# Amp_Measurement.net
KiCad netlist of a schematic drawn in Altium Designer
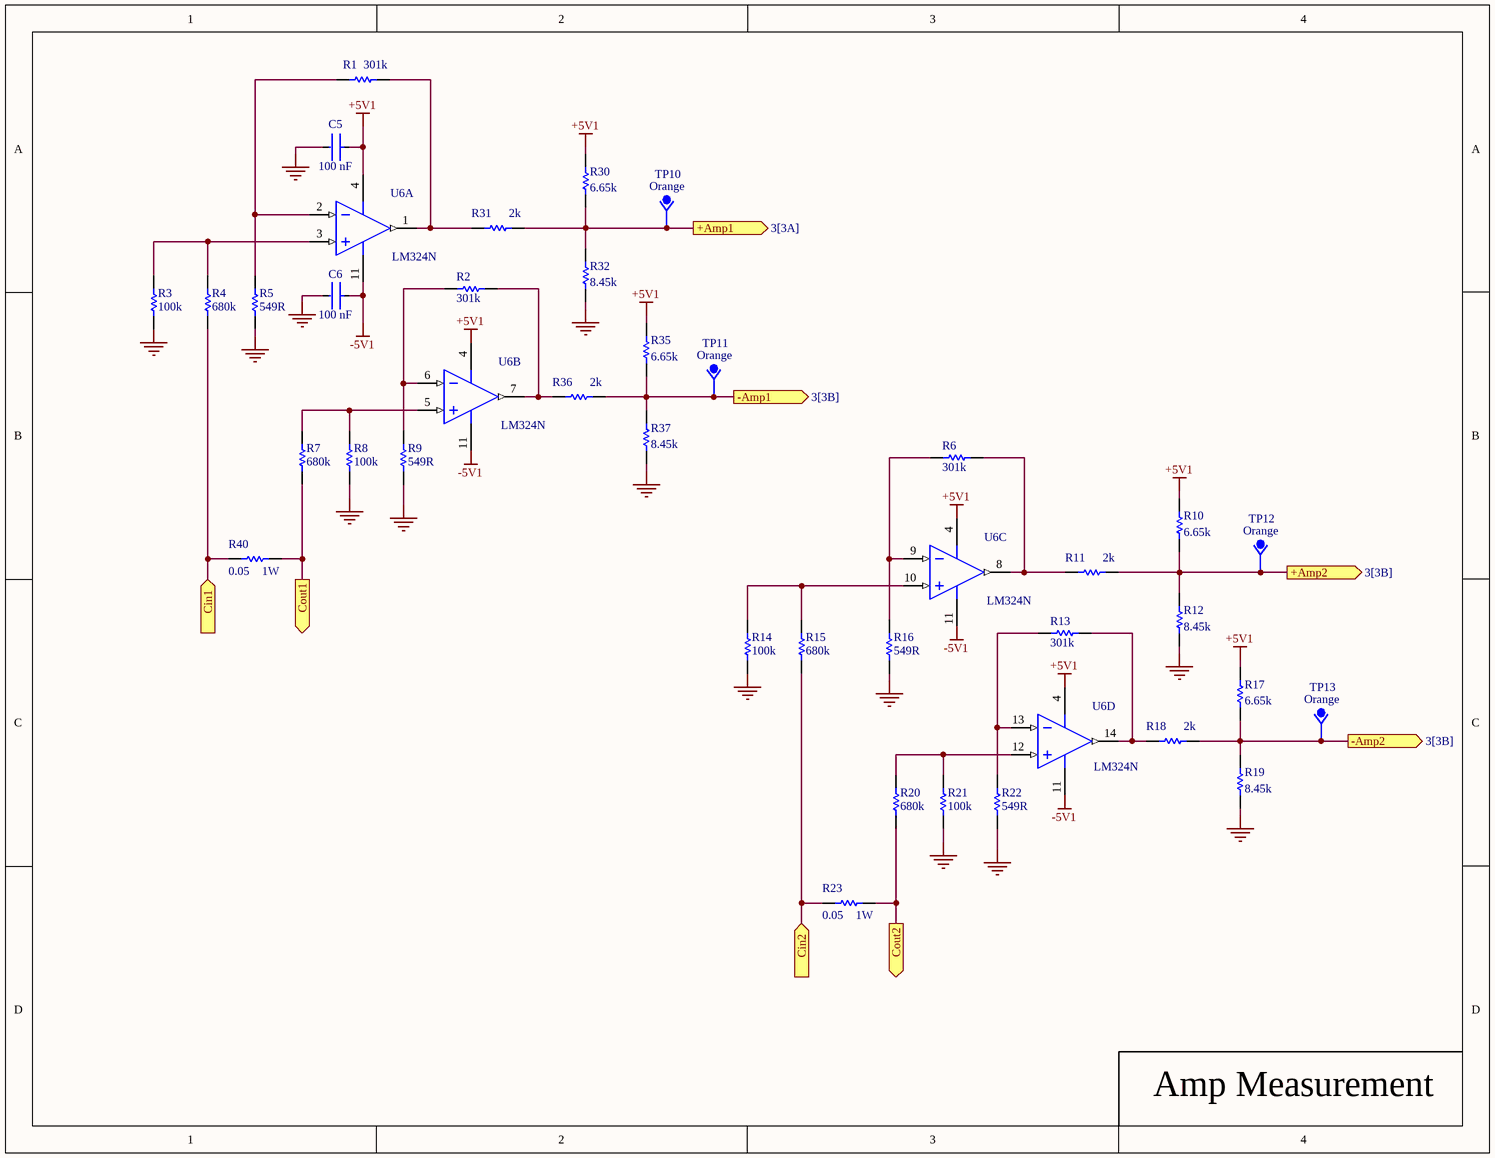
[diagram p0: Amp_Measurement.SchDoc]

(export (version "E")
  (design (tool "Eeschema 10.0.6"))
  (components
    (comp (ref "C5")
      (value "100 nF")
      (footprint "FP-CC0805-0_85-MFG")
      (description "CAP CER 0.1UF 16V X7R 0805")
      (fields
        (field (name "MANUFACTURER PART NUMBER") "CC0805KRX7R7BB104")
        (field (name "MANUFACTURER") "Yageo")
      )
      (libsource (lib "Altium Content Vault") (part "11868f565c42a9108669ba33697ecf6"))
    )
    (comp (ref "C6")
      (value "100 nF")
      (footprint "FP-CC0805-0_85-MFG")
      (description "CAP CER 0.1UF 16V X7R 0805")
      (fields
        (field (name "MANUFACTURER PART NUMBER") "CC0805KRX7R7BB104")
        (field (name "MANUFACTURER") "Yageo")
      )
      (libsource (lib "Altium Content Vault") (part "11868f565c42a9108669ba33697ecf6"))
    )
    (comp (ref "R1")
      (value "301k")
      (footprint "0805 Res")
      (fields
        (field (name "MANUFACTURER") "Stackpole Electronics")
        (field (name "MANUFACTURER PART NUMBER") "RMCF0805JT100K")
        (field (name "TOLERANCE") "5%")
        (field (name "PUBLISHER") "Altium Limited")
      )
      (libsource (lib "Miscellaneous Devices") (part "Res1"))
    )
    (comp (ref "R2")
      (value "301k")
      (footprint "0805 Res")
      (fields
        (field (name "MANUFACTURER") "Stackpole Electronics")
        (field (name "MANUFACTURER PART NUMBER") "RMCF0805JT100K")
        (field (name "TOLERANCE") "5%")
        (field (name "PUBLISHER") "Altium Limited")
      )
      (libsource (lib "Miscellaneous Devices") (part "Res1"))
    )
    (comp (ref "R3")
      (value "100k")
      (footprint "0805 Res")
      (fields
        (field (name "MANUFACTURER") "Stackpole Electronics")
        (field (name "MANUFACTURER PART NUMBER") "RMCF0805FT100K")
        (field (name "TOLERANCE") "1%")
        (field (name "PUBLISHER") "Altium Limited")
      )
      (libsource (lib "Miscellaneous Devices") (part "Res1"))
    )
    (comp (ref "R4")
      (value "680k")
      (footprint "0805 Res")
      (fields
        (field (name "MANUFACTURER") "Stackpole Electronics")
        (field (name "MANUFACTURER PART NUMBER") "RMCF0805FT680K")
        (field (name "TOLERANCE") "1%")
        (field (name "PUBLISHER") "Altium Limited")
      )
      (libsource (lib "Miscellaneous Devices") (part "Res1"))
    )
    (comp (ref "R5")
      (value "549R")
      (footprint "0805 Res")
      (fields
        (field (name "MANUFACTURER") "Stackpole Electronics")
        (field (name "MANUFACTURER PART NUMBER") "RMCF0805FT549R")
        (field (name "TOLERANCE") "1%")
      )
      (libsource (lib "Miscellaneous Devices") (part "Res1"))
    )
    (comp (ref "R6")
      (value "301k")
      (footprint "0805 Res")
      (fields
        (field (name "MANUFACTURER") "Stackpole Electronics")
        (field (name "MANUFACTURER PART NUMBER") "RMCF0805JT100K")
        (field (name "TOLERANCE") "5%")
        (field (name "PUBLISHER") "Altium Limited")
      )
      (libsource (lib "Miscellaneous Devices") (part "Res1"))
    )
    (comp (ref "R7")
      (value "680k")
      (footprint "0805 Res")
      (fields
        (field (name "MANUFACTURER") "Stackpole Electronics")
        (field (name "MANUFACTURER PART NUMBER") "RMCF0805FT680K")
        (field (name "TOLERANCE") "1%")
        (field (name "PUBLISHER") "Altium Limited")
      )
      (libsource (lib "Miscellaneous Devices") (part "Res1"))
    )
    (comp (ref "R8")
      (value "100k")
      (footprint "0805 Res")
      (fields
        (field (name "MANUFACTURER") "Stackpole Electronics")
        (field (name "MANUFACTURER PART NUMBER") "RMCF0805FT100K")
        (field (name "TOLERANCE") "1%")
        (field (name "PUBLISHER") "Altium Limited")
      )
      (libsource (lib "Miscellaneous Devices") (part "Res1"))
    )
    (comp (ref "R9")
      (value "549R")
      (footprint "0805 Res")
      (fields
        (field (name "MANUFACTURER") "Stackpole Electronics")
        (field (name "MANUFACTURER PART NUMBER") "RMCF0805FT549R")
        (field (name "TOLERANCE") "1%")
      )
      (libsource (lib "Miscellaneous Devices") (part "Res1"))
    )
    (comp (ref "R10")
      (value "6.65k")
      (footprint "0805 Res")
      (fields
        (field (name "MANUFACTURER") "Stackpole Electronics")
        (field (name "MANUFACTURER PART NUMBER") "RMCF0805FT6K65")
        (field (name "TOLERANCE") "1%")
      )
      (libsource (lib "Miscellaneous Devices") (part "Res1"))
    )
    (comp (ref "R11")
      (value "2k")
      (footprint "0805 Res")
      (fields
        (field (name "MANUFACTURER") "Stackpole Electronics")
        (field (name "MANUFACTURER PART NUMBER") "RMCF0805FT2K00")
        (field (name "TOLERANCE") "1%")
      )
      (libsource (lib "Miscellaneous Devices") (part "Res1"))
    )
    (comp (ref "R12")
      (value "8.45k")
      (footprint "0805 Res")
      (fields
        (field (name "MANUFACTURER") "Stackpole Electronics")
        (field (name "MANUFACTURER PART NUMBER") "RMCF0805FT8K45")
        (field (name "TOLERANCE") "1%")
      )
      (libsource (lib "Miscellaneous Devices") (part "Res1"))
    )
    (comp (ref "R13")
      (value "301k")
      (footprint "0805 Res")
      (fields
        (field (name "MANUFACTURER") "Stackpole Electronics")
        (field (name "MANUFACTURER PART NUMBER") "RMCF0805JT100K")
        (field (name "TOLERANCE") "5%")
        (field (name "PUBLISHER") "Altium Limited")
      )
      (libsource (lib "Miscellaneous Devices") (part "Res1"))
    )
    (comp (ref "R14")
      (value "100k")
      (footprint "0805 Res")
      (fields
        (field (name "MANUFACTURER") "Stackpole Electronics")
        (field (name "MANUFACTURER PART NUMBER") "RMCF0805FT100K")
        (field (name "TOLERANCE") "1%")
        (field (name "PUBLISHER") "Altium Limited")
      )
      (libsource (lib "Miscellaneous Devices") (part "Res1"))
    )
    (comp (ref "R15")
      (value "680k")
      (footprint "0805 Res")
      (fields
        (field (name "MANUFACTURER") "Stackpole Electronics")
        (field (name "MANUFACTURER PART NUMBER") "RMCF0805FT680K")
        (field (name "TOLERANCE") "1%")
        (field (name "PUBLISHER") "Altium Limited")
      )
      (libsource (lib "Miscellaneous Devices") (part "Res1"))
    )
    (comp (ref "R16")
      (value "549R")
      (footprint "0805 Res")
      (fields
        (field (name "MANUFACTURER") "Stackpole Electronics")
        (field (name "MANUFACTURER PART NUMBER") "RMCF0805FT549R")
        (field (name "TOLERANCE") "1%")
      )
      (libsource (lib "Miscellaneous Devices") (part "Res1"))
    )
    (comp (ref "R17")
      (value "6.65k")
      (footprint "0805 Res")
      (fields
        (field (name "MANUFACTURER") "Stackpole Electronics")
        (field (name "MANUFACTURER PART NUMBER") "RMCF0805FT6K65")
        (field (name "TOLERANCE") "1%")
      )
      (libsource (lib "Miscellaneous Devices") (part "Res1"))
    )
    (comp (ref "R18")
      (value "2k")
      (footprint "0805 Res")
      (fields
        (field (name "MANUFACTURER") "Stackpole Electronics")
        (field (name "MANUFACTURER PART NUMBER") "RMCF0805FT2K00")
        (field (name "TOLERANCE") "1%")
      )
      (libsource (lib "Miscellaneous Devices") (part "Res1"))
    )
    (comp (ref "R19")
      (value "8.45k")
      (footprint "0805 Res")
      (fields
        (field (name "MANUFACTURER") "Stackpole Electronics")
        (field (name "MANUFACTURER PART NUMBER") "RMCF0805FT8K45")
        (field (name "TOLERANCE") "1%")
      )
      (libsource (lib "Miscellaneous Devices") (part "Res1"))
    )
    (comp (ref "R20")
      (value "680k")
      (footprint "0805 Res")
      (fields
        (field (name "MANUFACTURER") "Stackpole Electronics")
        (field (name "MANUFACTURER PART NUMBER") "RMCF0805FT680K")
        (field (name "TOLERANCE") "1%")
        (field (name "PUBLISHER") "Altium Limited")
      )
      (libsource (lib "Miscellaneous Devices") (part "Res1"))
    )
    (comp (ref "R21")
      (value "100k")
      (footprint "0805 Res")
      (fields
        (field (name "MANUFACTURER") "Stackpole Electronics")
        (field (name "MANUFACTURER PART NUMBER") "RMCF0805FT100K")
        (field (name "TOLERANCE") "1%")
        (field (name "PUBLISHER") "Altium Limited")
      )
      (libsource (lib "Miscellaneous Devices") (part "Res1"))
    )
    (comp (ref "R22")
      (value "549R")
      (footprint "0805 Res")
      (fields
        (field (name "MANUFACTURER") "Stackpole Electronics")
        (field (name "MANUFACTURER PART NUMBER") "RMCF0805FT549R")
        (field (name "TOLERANCE") "1%")
      )
      (libsource (lib "Miscellaneous Devices") (part "Res1"))
    )
    (comp (ref "R23")
      (value "0.05")
      (footprint "1206 Res")
      (description "Fixed Resistor, Metal Glaze/thick Film, 1W, 0.05ohm, 1% +/-Tol, 75ppm/Cel, Surface Mount, 1206")
      (fields
        (field (name "MANUFACTURER") "Panasonic")
        (field (name "MANUFACTURER PART NUMBER") "ERJ-8CWFR050V")
        (field (name "POWER") "1W")
      )
      (libsource (lib "Miscellaneous Devices") (part "Res1"))
    )
    (comp (ref "R30")
      (value "6.65k")
      (footprint "0805 Res")
      (fields
        (field (name "MANUFACTURER") "Stackpole Electronics")
        (field (name "MANUFACTURER PART NUMBER") "RMCF0805FT6K65")
        (field (name "TOLERANCE") "1%")
      )
      (libsource (lib "Miscellaneous Devices") (part "Res1"))
    )
    (comp (ref "R31")
      (value "2k")
      (footprint "0805 Res")
      (fields
        (field (name "MANUFACTURER") "Stackpole Electronics")
        (field (name "MANUFACTURER PART NUMBER") "RMCF0805FT2K00")
        (field (name "TOLERANCE") "1%")
      )
      (libsource (lib "Miscellaneous Devices") (part "Res1"))
    )
    (comp (ref "R32")
      (value "8.45k")
      (footprint "0805 Res")
      (fields
        (field (name "MANUFACTURER") "Stackpole Electronics")
        (field (name "MANUFACTURER PART NUMBER") "RMCF0805FT8K45")
        (field (name "TOLERANCE") "1%")
      )
      (libsource (lib "Miscellaneous Devices") (part "Res1"))
    )
    (comp (ref "R35")
      (value "6.65k")
      (footprint "0805 Res")
      (fields
        (field (name "MANUFACTURER") "Stackpole Electronics")
        (field (name "MANUFACTURER PART NUMBER") "RMCF0805FT6K65")
        (field (name "TOLERANCE") "1%")
      )
      (libsource (lib "Miscellaneous Devices") (part "Res1"))
    )
    (comp (ref "R36")
      (value "2k")
      (footprint "0805 Res")
      (fields
        (field (name "MANUFACTURER") "Stackpole Electronics")
        (field (name "MANUFACTURER PART NUMBER") "RMCF0805FT2K00")
        (field (name "TOLERANCE") "1%")
      )
      (libsource (lib "Miscellaneous Devices") (part "Res1"))
    )
    (comp (ref "R37")
      (value "8.45k")
      (footprint "0805 Res")
      (fields
        (field (name "MANUFACTURER") "Stackpole Electronics")
        (field (name "MANUFACTURER PART NUMBER") "RMCF0805FT8K45")
        (field (name "TOLERANCE") "1%")
      )
      (libsource (lib "Miscellaneous Devices") (part "Res1"))
    )
    (comp (ref "R40")
      (value "0.05")
      (footprint "1206 Res")
      (description "Fixed Resistor, Metal Glaze/thick Film, 1W, 0.05ohm, 1% +/-Tol, 75ppm/Cel, Surface Mount, 1206")
      (fields
        (field (name "MANUFACTURER") "Panasonic")
        (field (name "MANUFACTURER PART NUMBER") "ERJ-8CWFR050V")
        (field (name "POWER") "1W")
      )
      (libsource (lib "Miscellaneous Devices") (part "Res1"))
    )
    (comp (ref "TP10")
      (value "TP (Orange)")
      (footprint "ORANGETP")
      (description "Orange Test Point")
      (fields
        (field (name "MANUFACTURER") "Keystone")
        (field (name "MANUFACTURER PART NUMBER") "5003")
        (field (name "COLOR") "Orange")
      )
      (libsource (lib "*") (part "TP"))
    )
    (comp (ref "TP11")
      (value "TP (Orange)")
      (footprint "ORANGETP")
      (description "Orange Test Point")
      (fields
        (field (name "MANUFACTURER") "Keystone")
        (field (name "MANUFACTURER PART NUMBER") "5003")
        (field (name "COLOR") "Orange")
      )
      (libsource (lib "*") (part "TP"))
    )
    (comp (ref "TP12")
      (value "TP (Orange)")
      (footprint "ORANGETP")
      (description "Orange Test Point")
      (fields
        (field (name "MANUFACTURER") "Keystone")
        (field (name "MANUFACTURER PART NUMBER") "5003")
        (field (name "COLOR") "Orange")
      )
      (libsource (lib "*") (part "TP"))
    )
    (comp (ref "TP13")
      (value "TP (Orange)")
      (footprint "ORANGETP")
      (description "Orange Test Point")
      (fields
        (field (name "MANUFACTURER") "Keystone")
        (field (name "MANUFACTURER PART NUMBER") "5003")
        (field (name "COLOR") "Orange")
      )
      (libsource (lib "*") (part "TP"))
    )
    (comp (ref "U6")
      (value "4CH Op-Amp")
      (footprint "N0014A")
      (description "Low Power Quad Operational Amplifier, 14-pin MDIP")
      (fields
        (field (name "MANUFACTURER") "Texas Instruments")
        (field (name "MANUFACTURER PART NUMBER") "LM324N")
      )
      (libsource (lib "Altium Content Vault") (part "AMP-OPA-LM124-14"))
    )
  )
  (nets
    (net (code "1") (name "+5V1") (class "Default")
      (node (ref "C5") (pin "1") (pinfunction "1_1") (pintype "passive"))
      (node (ref "R10") (pin "2") (pinfunction "2_2") (pintype "passive"))
      (node (ref "R17") (pin "2") (pinfunction "2_2") (pintype "passive"))
      (node (ref "R30") (pin "2") (pinfunction "2_2") (pintype "passive"))
      (node (ref "R35") (pin "2") (pinfunction "2_2") (pintype "passive"))
      (node (ref "U6") (pin "4") (pinfunction "V+_4") (pintype "power_in"))
    )
    (net (code "2") (name "-5V1") (class "Default")
      (node (ref "C6") (pin "1") (pinfunction "1_1") (pintype "passive"))
      (node (ref "U6") (pin "11") (pinfunction "GND_11") (pintype "power_in"))
    )
    (net (code "3") (name "/+Amp1") (class "Default")
      (node (ref "R30") (pin "1") (pinfunction "1_1") (pintype "passive"))
      (node (ref "R31") (pin "1") (pinfunction "1_1") (pintype "passive"))
      (node (ref "R32") (pin "2") (pinfunction "2_2") (pintype "passive"))
      (node (ref "TP10") (pin "1") (pinfunction "TP_1") (pintype "passive"))
    )
    (net (code "4") (name "/+Amp2") (class "Default")
      (node (ref "R10") (pin "1") (pinfunction "1_1") (pintype "passive"))
      (node (ref "R11") (pin "1") (pinfunction "1_1") (pintype "passive"))
      (node (ref "R12") (pin "2") (pinfunction "2_2") (pintype "passive"))
      (node (ref "TP12") (pin "1") (pinfunction "TP_1") (pintype "passive"))
    )
    (net (code "5") (name "/-Amp1") (class "Default")
      (node (ref "R35") (pin "1") (pinfunction "1_1") (pintype "passive"))
      (node (ref "R36") (pin "1") (pinfunction "1_1") (pintype "passive"))
      (node (ref "R37") (pin "2") (pinfunction "2_2") (pintype "passive"))
      (node (ref "TP11") (pin "1") (pinfunction "TP_1") (pintype "passive"))
    )
    (net (code "6") (name "/-Amp2") (class "Default")
      (node (ref "R17") (pin "1") (pinfunction "1_1") (pintype "passive"))
      (node (ref "R18") (pin "1") (pinfunction "1_1") (pintype "passive"))
      (node (ref "R19") (pin "2") (pinfunction "2_2") (pintype "passive"))
      (node (ref "TP13") (pin "1") (pinfunction "TP_1") (pintype "passive"))
    )
    (net (code "7") (name "/Cin1") (class "Default")
      (node (ref "R4") (pin "1") (pinfunction "1_1") (pintype "passive"))
      (node (ref "R40") (pin "1") (pinfunction "1_1") (pintype "passive"))
    )
    (net (code "8") (name "/Cin2") (class "Default")
      (node (ref "R15") (pin "1") (pinfunction "1_1") (pintype "passive"))
      (node (ref "R23") (pin "1") (pinfunction "1_1") (pintype "passive"))
    )
    (net (code "9") (name "/Cout1") (class "Default")
      (node (ref "R40") (pin "2") (pinfunction "2_2") (pintype "passive"))
      (node (ref "R7") (pin "1") (pinfunction "1_1") (pintype "passive"))
    )
    (net (code "10") (name "/Cout2") (class "Default")
      (node (ref "R20") (pin "1") (pinfunction "1_1") (pintype "passive"))
      (node (ref "R23") (pin "2") (pinfunction "2_2") (pintype "passive"))
    )
    (net (code "11") (name "GND") (class "Default")
      (node (ref "C5") (pin "2") (pinfunction "2_2") (pintype "passive"))
      (node (ref "C6") (pin "2") (pinfunction "2_2") (pintype "passive"))
      (node (ref "R12") (pin "1") (pinfunction "1_1") (pintype "passive"))
      (node (ref "R14") (pin "2") (pinfunction "2_2") (pintype "passive"))
      (node (ref "R16") (pin "1") (pinfunction "1_1") (pintype "passive"))
      (node (ref "R19") (pin "1") (pinfunction "1_1") (pintype "passive"))
      (node (ref "R21") (pin "2") (pinfunction "2_2") (pintype "passive"))
      (node (ref "R22") (pin "1") (pinfunction "1_1") (pintype "passive"))
      (node (ref "R3") (pin "2") (pinfunction "2_2") (pintype "passive"))
      (node (ref "R32") (pin "1") (pinfunction "1_1") (pintype "passive"))
      (node (ref "R37") (pin "1") (pinfunction "1_1") (pintype "passive"))
      (node (ref "R5") (pin "1") (pinfunction "1_1") (pintype "passive"))
      (node (ref "R8") (pin "2") (pinfunction "2_2") (pintype "passive"))
      (node (ref "R9") (pin "1") (pinfunction "1_1") (pintype "passive"))
    )
    (net (code "12") (name "Net-(U6A-IN1+)") (class "Default")
      (node (ref "R3") (pin "1") (pinfunction "1_1") (pintype "passive"))
      (node (ref "R4") (pin "2") (pinfunction "2_2") (pintype "passive"))
      (node (ref "U6") (pin "3") (pinfunction "IN1+_3") (pintype "input"))
    )
    (net (code "13") (name "Net-(U6A-IN1-)") (class "Default")
      (node (ref "R1") (pin "2") (pinfunction "2_2") (pintype "passive"))
      (node (ref "R5") (pin "2") (pinfunction "2_2") (pintype "passive"))
      (node (ref "U6") (pin "2") (pinfunction "IN1-_2") (pintype "input"))
    )
    (net (code "14") (name "Net-(U6A-OUT1)") (class "Default")
      (node (ref "R1") (pin "1") (pinfunction "1_1") (pintype "passive"))
      (node (ref "R31") (pin "2") (pinfunction "2_2") (pintype "passive"))
      (node (ref "U6") (pin "1") (pinfunction "OUT1_1") (pintype "output"))
    )
    (net (code "15") (name "Net-(U6B-IN2+)") (class "Default")
      (node (ref "R7") (pin "2") (pinfunction "2_2") (pintype "passive"))
      (node (ref "R8") (pin "1") (pinfunction "1_1") (pintype "passive"))
      (node (ref "U6") (pin "5") (pinfunction "IN2+_5") (pintype "input"))
    )
    (net (code "16") (name "Net-(U6B-IN2-)") (class "Default")
      (node (ref "R2") (pin "2") (pinfunction "2_2") (pintype "passive"))
      (node (ref "R9") (pin "2") (pinfunction "2_2") (pintype "passive"))
      (node (ref "U6") (pin "6") (pinfunction "IN2-_6") (pintype "input"))
    )
    (net (code "17") (name "Net-(U6B-OUT2)") (class "Default")
      (node (ref "R2") (pin "1") (pinfunction "1_1") (pintype "passive"))
      (node (ref "R36") (pin "2") (pinfunction "2_2") (pintype "passive"))
      (node (ref "U6") (pin "7") (pinfunction "OUT2_7") (pintype "output"))
    )
    (net (code "18") (name "Net-(U6C-IN3+)") (class "Default")
      (node (ref "R14") (pin "1") (pinfunction "1_1") (pintype "passive"))
      (node (ref "R15") (pin "2") (pinfunction "2_2") (pintype "passive"))
      (node (ref "U6") (pin "10") (pinfunction "IN3+_10") (pintype "input"))
    )
    (net (code "19") (name "Net-(U6C-IN3-)") (class "Default")
      (node (ref "R16") (pin "2") (pinfunction "2_2") (pintype "passive"))
      (node (ref "R6") (pin "2") (pinfunction "2_2") (pintype "passive"))
      (node (ref "U6") (pin "9") (pinfunction "IN3-_9") (pintype "input"))
    )
    (net (code "20") (name "Net-(U6C-OUT3)") (class "Default")
      (node (ref "R11") (pin "2") (pinfunction "2_2") (pintype "passive"))
      (node (ref "R6") (pin "1") (pinfunction "1_1") (pintype "passive"))
      (node (ref "U6") (pin "8") (pinfunction "OUT3_8") (pintype "output"))
    )
    (net (code "21") (name "Net-(U6D-IN4+)") (class "Default")
      (node (ref "R20") (pin "2") (pinfunction "2_2") (pintype "passive"))
      (node (ref "R21") (pin "1") (pinfunction "1_1") (pintype "passive"))
      (node (ref "U6") (pin "12") (pinfunction "IN4+_12") (pintype "input"))
    )
    (net (code "22") (name "Net-(U6D-IN4-)") (class "Default")
      (node (ref "R13") (pin "2") (pinfunction "2_2") (pintype "passive"))
      (node (ref "R22") (pin "2") (pinfunction "2_2") (pintype "passive"))
      (node (ref "U6") (pin "13") (pinfunction "IN4-_13") (pintype "input"))
    )
    (net (code "23") (name "Net-(U6D-OUT4)") (class "Default")
      (node (ref "R13") (pin "1") (pinfunction "1_1") (pintype "passive"))
      (node (ref "R18") (pin "2") (pinfunction "2_2") (pintype "passive"))
      (node (ref "U6") (pin "14") (pinfunction "OUT4_14") (pintype "output"))
    )
  )
)
